# Audio_input.net
KiCad netlist of a schematic drawn in EAGLE
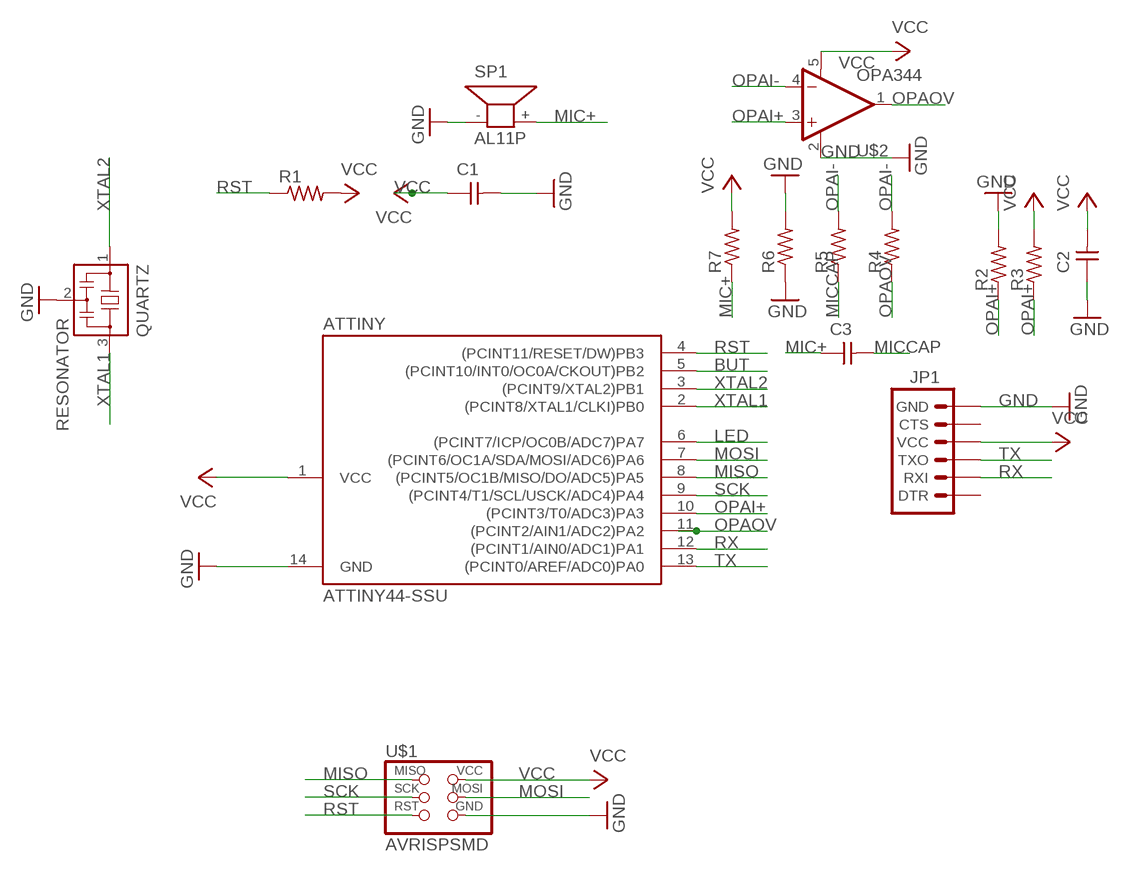
[diagram p0: schematic, sheet 1]

(export (version "E")
  (design (tool "Eeschema 10.0.6"))
  (components
    (comp (ref "ATTINY")
      (value "ATTINY44-SSU")
      (footprint "eagle-import:SOIC14")
      (libsource (lib "eagle-import") (part "ATTINY44-SSU"))
    )
    (comp (ref "C1")
      (value "UNPOLARIZED_CAPACITOR1206")
      (footprint "eagle-import:1206")
      (libsource (lib "eagle-import") (part "UNPOLARIZED_CAPACITOR1206"))
    )
    (comp (ref "C2")
      (value "UNPOLARIZED_CAPACITOR1206")
      (footprint "eagle-import:1206")
      (libsource (lib "eagle-import") (part "UNPOLARIZED_CAPACITOR1206"))
    )
    (comp (ref "C3")
      (value "UNPOLARIZED_CAPACITOR1206")
      (footprint "eagle-import:1206")
      (libsource (lib "eagle-import") (part "UNPOLARIZED_CAPACITOR1206"))
    )
    (comp (ref "JP1")
      (value "ARDUINO_SERIAL_PROGRAMLONGPADS")
      (footprint "eagle-import:1X06_LONGPADS")
      (libsource (lib "eagle-import") (part "ARDUINO_SERIAL_PROGRAMLONGPADS"))
    )
    (comp (ref "QUARTZ")
      (value "RESONATOR")
      (footprint "eagle-import:EFOBM")
      (libsource (lib "eagle-import") (part "RESONATOR"))
    )
    (comp (ref "R1")
      (value "RESISTOR1206")
      (footprint "eagle-import:1206")
      (libsource (lib "eagle-import") (part "RESISTOR1206"))
    )
    (comp (ref "R2")
      (value "RESISTOR1206")
      (footprint "eagle-import:1206")
      (libsource (lib "eagle-import") (part "RESISTOR1206"))
    )
    (comp (ref "R3")
      (value "RESISTOR1206")
      (footprint "eagle-import:1206")
      (libsource (lib "eagle-import") (part "RESISTOR1206"))
    )
    (comp (ref "R4")
      (value "RESISTOR1206")
      (footprint "eagle-import:1206")
      (libsource (lib "eagle-import") (part "RESISTOR1206"))
    )
    (comp (ref "R5")
      (value "RESISTOR1206")
      (footprint "eagle-import:1206")
      (libsource (lib "eagle-import") (part "RESISTOR1206"))
    )
    (comp (ref "R6")
      (value "RESISTOR1206")
      (footprint "eagle-import:1206")
      (libsource (lib "eagle-import") (part "RESISTOR1206"))
    )
    (comp (ref "R7")
      (value "RESISTOR1206")
      (footprint "eagle-import:1206")
      (libsource (lib "eagle-import") (part "RESISTOR1206"))
    )
    (comp (ref "SP1")
      (value "AL11P")
      (footprint "eagle-import:AL11P")
      (libsource (lib "eagle-import") (part "AL11P"))
    )
    (comp (ref "U$1")
      (value "AVRISPSMD")
      (footprint "eagle-import:2X03SMD")
      (libsource (lib "eagle-import") (part "AVRISPSMD"))
    )
    (comp (ref "U$2")
      (value "OPA344")
      (footprint "eagle-import:SOT23-5")
      (libsource (lib "eagle-import") (part "OPA344"))
    )
  )
  (nets
    (net (code "1") (name "/BUT") (class "Default")
      (node (ref "ATTINY") (pin "5") (pinfunction "(PCINT10/INT0/OC0A/CKOUT)PB2_5") (pintype "bidirectional"))
    )
    (net (code "2") (name "/LED") (class "Default")
      (node (ref "ATTINY") (pin "6") (pinfunction "(PCINT7/ICP/OC0B/ADC7)PA7_6") (pintype "bidirectional"))
    )
    (net (code "3") (name "/MIC+") (class "Default")
      (node (ref "C3") (pin "1") (pinfunction "1_1") (pintype "passive"))
      (node (ref "R7") (pin "1") (pinfunction "1_1") (pintype "passive"))
      (node (ref "SP1") (pin "+") (pinfunction "2_+") (pintype "passive"))
    )
    (net (code "4") (name "/MICCAP") (class "Default")
      (node (ref "C3") (pin "2") (pinfunction "2_2") (pintype "passive"))
      (node (ref "R5") (pin "1") (pinfunction "1_1") (pintype "passive"))
    )
    (net (code "5") (name "/MISO") (class "Default")
      (node (ref "ATTINY") (pin "8") (pinfunction "(PCINT5/OC1B/MISO/DO/ADC5)PA5_8") (pintype "bidirectional"))
      (node (ref "U$1") (pin "1") (pinfunction "MISO_1") (pintype "passive"))
    )
    (net (code "6") (name "/MOSI") (class "Default")
      (node (ref "ATTINY") (pin "7") (pinfunction "(PCINT6/OC1A/SDA/MOSI/ADC6)PA6_7") (pintype "bidirectional"))
      (node (ref "U$1") (pin "4") (pinfunction "MOSI_4") (pintype "passive"))
    )
    (net (code "7") (name "/OPAI+") (class "Default")
      (node (ref "ATTINY") (pin "10") (pinfunction "(PCINT3/T0/ADC3)PA3_10") (pintype "bidirectional"))
      (node (ref "R2") (pin "1") (pinfunction "1_1") (pintype "passive"))
      (node (ref "R3") (pin "1") (pinfunction "1_1") (pintype "passive"))
      (node (ref "U$2") (pin "3") (pinfunction "+IN_3") (pintype "input"))
    )
    (net (code "8") (name "/OPAI-") (class "Default")
      (node (ref "R4") (pin "2") (pinfunction "2_2") (pintype "passive"))
      (node (ref "R5") (pin "2") (pinfunction "2_2") (pintype "passive"))
      (node (ref "U$2") (pin "4") (pinfunction "-IN_4") (pintype "input"))
    )
    (net (code "9") (name "/OPAOV") (class "Default")
      (node (ref "ATTINY") (pin "11") (pinfunction "(PCINT2/AIN1/ADC2)PA2_11") (pintype "bidirectional"))
      (node (ref "R4") (pin "1") (pinfunction "1_1") (pintype "passive"))
      (node (ref "U$2") (pin "1") (pinfunction "OUT_1") (pintype "output"))
    )
    (net (code "10") (name "/RST") (class "Default")
      (node (ref "ATTINY") (pin "4") (pinfunction "(PCINT11/RESET/DW)PB3_4") (pintype "bidirectional"))
      (node (ref "R1") (pin "1") (pinfunction "1_1") (pintype "passive"))
      (node (ref "U$1") (pin "5") (pinfunction "RST_5") (pintype "passive"))
    )
    (net (code "11") (name "/RX") (class "Default")
      (node (ref "ATTINY") (pin "12") (pinfunction "(PCINT1/AIN0/ADC1)PA1_12") (pintype "bidirectional"))
      (node (ref "JP1") (pin "2") (pinfunction "RXI_2") (pintype "passive"))
    )
    (net (code "12") (name "/SCK") (class "Default")
      (node (ref "ATTINY") (pin "9") (pinfunction "(PCINT4/T1/SCL/USCK/ADC4)PA4_9") (pintype "bidirectional"))
      (node (ref "U$1") (pin "3") (pinfunction "SCK_3") (pintype "passive"))
    )
    (net (code "13") (name "/TX") (class "Default")
      (node (ref "ATTINY") (pin "13") (pinfunction "(PCINT0/AREF/ADC0)PA0_13") (pintype "bidirectional"))
      (node (ref "JP1") (pin "3") (pinfunction "TXO_3") (pintype "passive"))
    )
    (net (code "14") (name "/XTAL1") (class "Default")
      (node (ref "ATTINY") (pin "2") (pinfunction "(PCINT8/XTAL1/CLKI)PB0_2") (pintype "bidirectional"))
      (node (ref "QUARTZ") (pin "3") (pinfunction "3_3") (pintype "passive"))
    )
    (net (code "15") (name "/XTAL2") (class "Default")
      (node (ref "ATTINY") (pin "3") (pinfunction "(PCINT9/XTAL2)PB1_3") (pintype "bidirectional"))
      (node (ref "QUARTZ") (pin "1") (pinfunction "1_1") (pintype "passive"))
    )
    (net (code "16") (name "GND") (class "Default")
      (node (ref "ATTINY") (pin "14") (pinfunction "GND_14") (pintype "power_in"))
      (node (ref "C1") (pin "2") (pinfunction "2_2") (pintype "passive"))
      (node (ref "C2") (pin "1") (pinfunction "1_1") (pintype "passive"))
      (node (ref "JP1") (pin "6") (pinfunction "GND_6") (pintype "passive"))
      (node (ref "QUARTZ") (pin "2") (pinfunction "2_2") (pintype "passive"))
      (node (ref "R2") (pin "2") (pinfunction "2_2") (pintype "passive"))
      (node (ref "R6") (pin "1") (pinfunction "1_1") (pintype "passive"))
      (node (ref "R6") (pin "2") (pinfunction "2_2") (pintype "passive"))
      (node (ref "SP1") (pin "-") (pinfunction "1_-") (pintype "passive"))
      (node (ref "U$1") (pin "6") (pinfunction "GND_6") (pintype "passive"))
      (node (ref "U$2") (pin "2") (pinfunction "V-_2") (pintype "power_in"))
    )
    (net (code "17") (name "VCC") (class "Default")
      (node (ref "ATTINY") (pin "1") (pinfunction "VCC_1") (pintype "power_in"))
      (node (ref "C1") (pin "1") (pinfunction "1_1") (pintype "passive"))
      (node (ref "C2") (pin "2") (pinfunction "2_2") (pintype "passive"))
      (node (ref "JP1") (pin "4") (pinfunction "VCC_4") (pintype "passive"))
      (node (ref "R1") (pin "2") (pinfunction "2_2") (pintype "passive"))
      (node (ref "R3") (pin "2") (pinfunction "2_2") (pintype "passive"))
      (node (ref "R7") (pin "2") (pinfunction "2_2") (pintype "passive"))
      (node (ref "U$1") (pin "2") (pinfunction "VCC_2") (pintype "passive"))
      (node (ref "U$2") (pin "5") (pinfunction "V+_5") (pintype "power_in"))
    )
    (net (code "18") (name "unconnected-(JP1-CTS-Pad5)") (class "Default")
      (node (ref "JP1") (pin "5") (pinfunction "CTS_5") (pintype "passive"))
    )
    (net (code "19") (name "unconnected-(JP1-DTR-Pad1)") (class "Default")
      (node (ref "JP1") (pin "1") (pinfunction "DTR_1") (pintype "passive"))
    )
  )
)
